# demo_dermis_main_testboard.net
KiCad netlist of a schematic drawn in Altium Designer
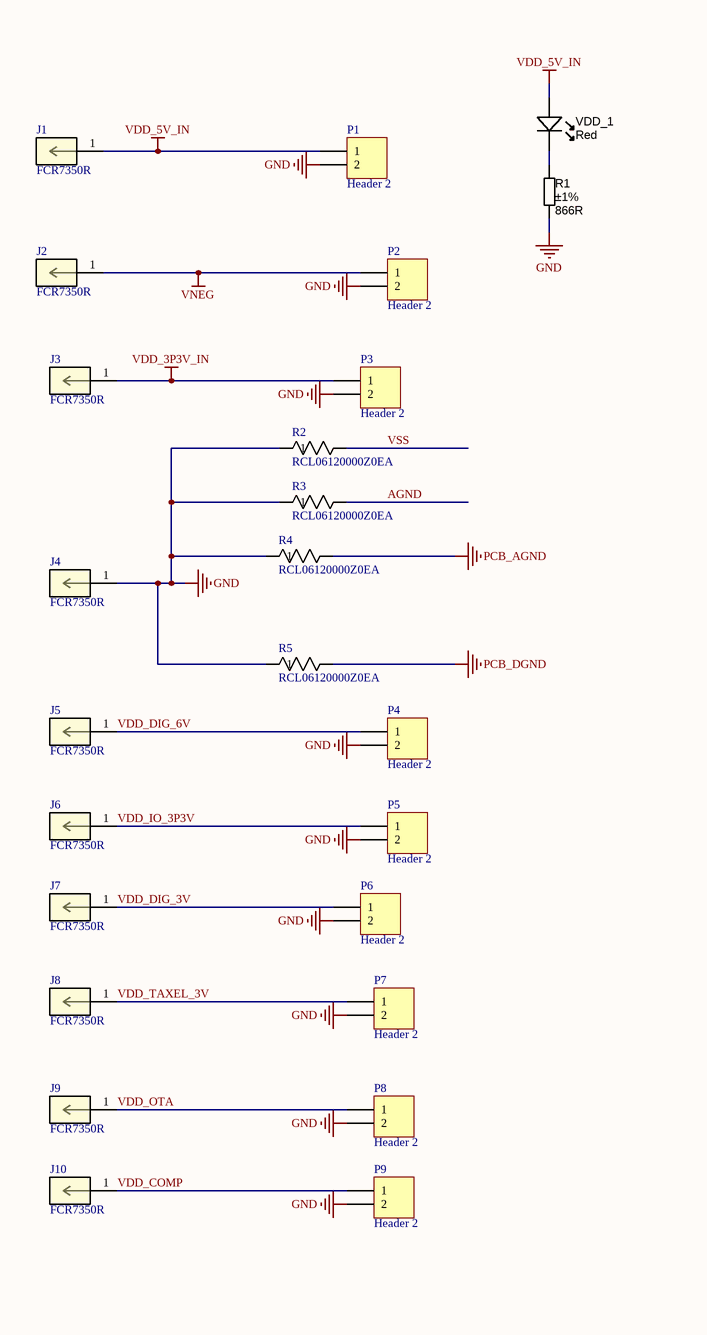
[diagram p0: demo_dermis_main_testboard.SchDoc, top left]
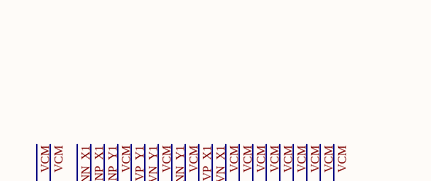
[diagram p1: demo_dermis_main_testboard.SchDoc, top right]
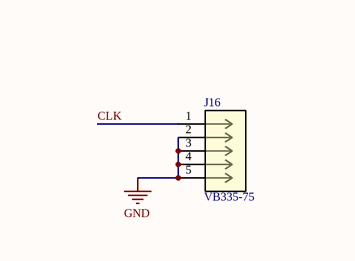
[diagram p2: demo_dermis_main_testboard.SchDoc, bottom middle]
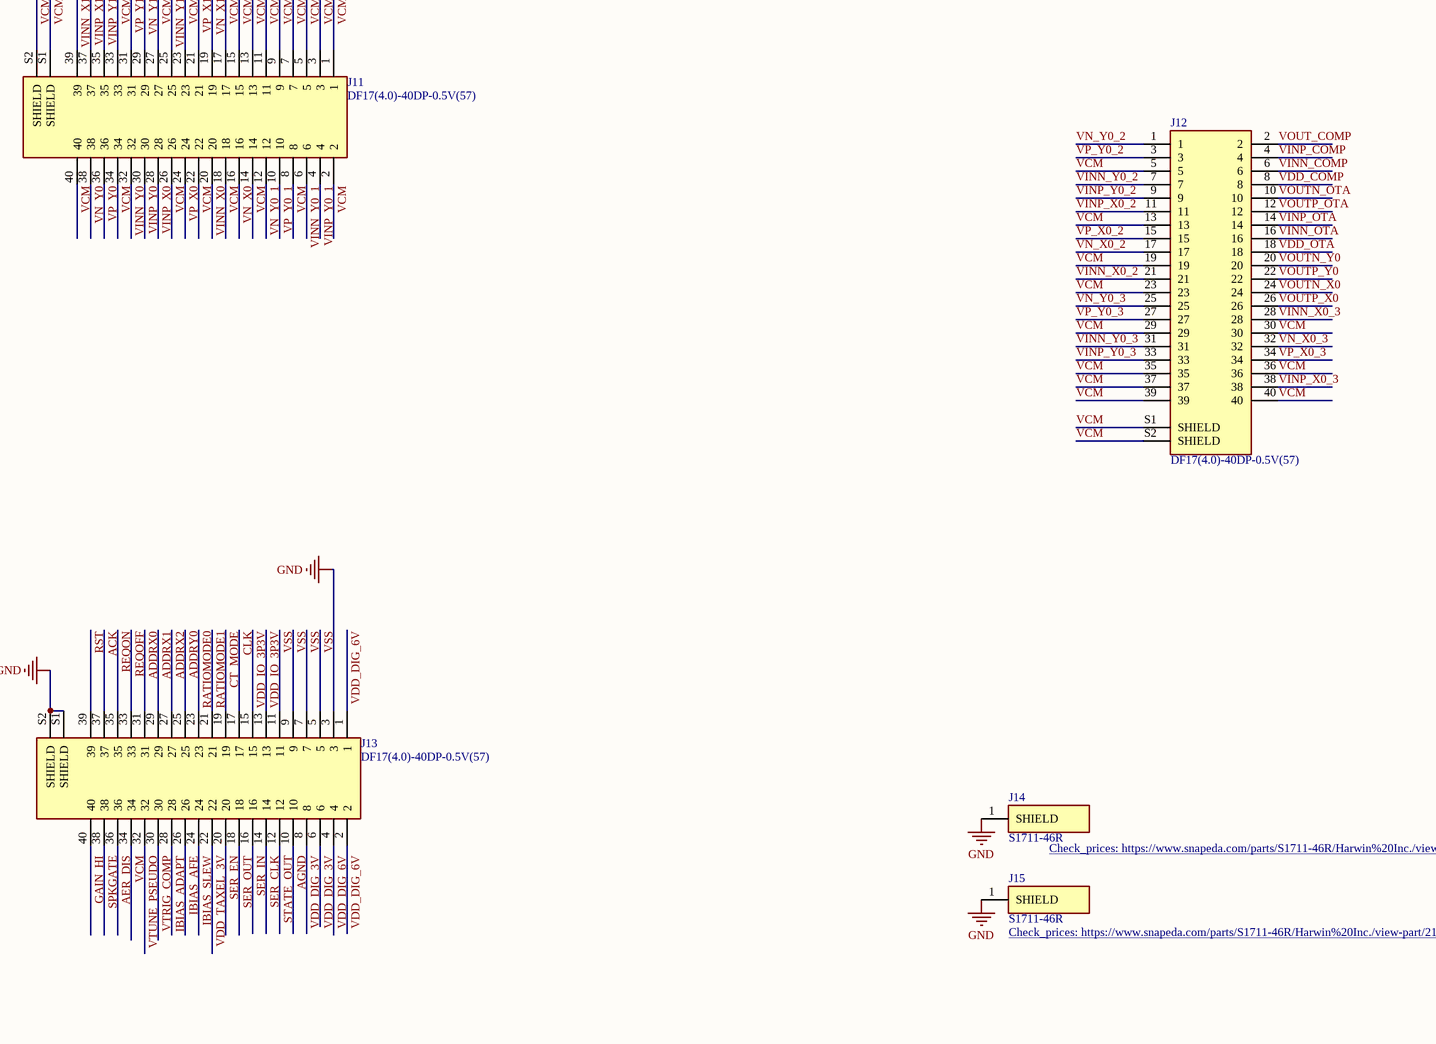
[diagram p3: demo_dermis_main_testboard.SchDoc, bottom right]

(export (version "E")
  (design (tool "Eeschema 10.0.6"))
  (components
    (comp (ref "J1")
      (value "FCR7350R")
      (footprint "CONN1_FCR7350R_CLF")
      (description "No Description Available")
      (fields (field (name "COPYRIGHT") "Copyright (C) 2022 Ultra Librarian. All rights reserved."))
      (libsource (lib "FCR7350B") (part "FCR7350R"))
    )
    (comp (ref "J2")
      (value "FCR7350R")
      (footprint "CONN1_FCR7350R_CLF")
      (description "No Description Available")
      (fields (field (name "COPYRIGHT") "Copyright (C) 2022 Ultra Librarian. All rights reserved."))
      (libsource (lib "FCR7350B") (part "FCR7350R"))
    )
    (comp (ref "J3")
      (value "FCR7350R")
      (footprint "CONN1_FCR7350R_CLF")
      (description "No Description Available")
      (fields (field (name "COPYRIGHT") "Copyright (C) 2022 Ultra Librarian. All rights reserved."))
      (libsource (lib "FCR7350B") (part "FCR7350R"))
    )
    (comp (ref "J4")
      (value "FCR7350R")
      (footprint "CONN1_FCR7350R_CLF")
      (description "No Description Available")
      (fields (field (name "COPYRIGHT") "Copyright (C) 2022 Ultra Librarian. All rights reserved."))
      (libsource (lib "FCR7350B") (part "FCR7350R"))
    )
    (comp (ref "J5")
      (value "FCR7350R")
      (footprint "CONN1_FCR7350R_CLF")
      (description "No Description Available")
      (fields (field (name "COPYRIGHT") "Copyright (C) 2022 Ultra Librarian. All rights reserved."))
      (libsource (lib "FCR7350B") (part "FCR7350R"))
    )
    (comp (ref "J6")
      (value "FCR7350R")
      (footprint "CONN1_FCR7350R_CLF")
      (description "No Description Available")
      (fields (field (name "COPYRIGHT") "Copyright (C) 2022 Ultra Librarian. All rights reserved."))
      (libsource (lib "FCR7350B") (part "FCR7350R"))
    )
    (comp (ref "J7")
      (value "FCR7350R")
      (footprint "CONN1_FCR7350R_CLF")
      (description "No Description Available")
      (fields (field (name "COPYRIGHT") "Copyright (C) 2022 Ultra Librarian. All rights reserved."))
      (libsource (lib "FCR7350B") (part "FCR7350R"))
    )
    (comp (ref "J8")
      (value "FCR7350R")
      (footprint "CONN1_FCR7350R_CLF")
      (description "No Description Available")
      (fields (field (name "COPYRIGHT") "Copyright (C) 2022 Ultra Librarian. All rights reserved."))
      (libsource (lib "FCR7350B") (part "FCR7350R"))
    )
    (comp (ref "J9")
      (value "FCR7350R")
      (footprint "CONN1_FCR7350R_CLF")
      (description "No Description Available")
      (fields (field (name "COPYRIGHT") "Copyright (C) 2022 Ultra Librarian. All rights reserved."))
      (libsource (lib "FCR7350B") (part "FCR7350R"))
    )
    (comp (ref "J10")
      (value "FCR7350R")
      (footprint "CONN1_FCR7350R_CLF")
      (description "No Description Available")
      (fields (field (name "COPYRIGHT") "Copyright (C) 2022 Ultra Librarian. All rights reserved."))
      (libsource (lib "FCR7350B") (part "FCR7350R"))
    )
    (comp (ref "J11")
      (value "DF17(4.0)-40DP-0.5V(57)")
      (footprint "HRS_DF17(4.0)-40DP-0.5V(57)")
      (libsource (lib "DF17_4.0_-40DP-0.5V_57_") (part "DF17(4.0)-40DP-0.5V(57)"))
    )
    (comp (ref "J12")
      (value "DF17(4.0)-40DP-0.5V(57)")
      (footprint "HRS_DF17(4.0)-40DP-0.5V(57)")
      (libsource (lib "") (part "DF17(4.0)-40DP-0.5V(57)_1"))
    )
    (comp (ref "J13")
      (value "DF17(4.0)-40DP-0.5V(57)")
      (footprint "HRS_DF17(4.0)-40DP-0.5V(57)")
      (libsource (lib "DF17_4.0_-40DP-0.5V_57_") (part "DF17(4.0)-40DP-0.5V(57)"))
    )
    (comp (ref "J14")
      (value "S1711-46R")
      (footprint "HARWIN_S1711-46R")
      (description "RFI SHIELD CLIP TIN SMD")
      (fields
        (field (name "MF") "Harwin Inc.")
        (field (name "CHECK_PRICES") "https://www.snapeda.com/parts/S1711-46R/Harwin%20Inc./view-part/2172610/?ref=eda")
      )
      (libsource (lib "S1711-46R") (part "S1711-46R"))
    )
    (comp (ref "J15")
      (value "S1711-46R")
      (footprint "HARWIN_S1711-46R")
      (description "RFI SHIELD CLIP TIN SMD")
      (fields
        (field (name "MF") "Harwin Inc.")
        (field (name "CHECK_PRICES") "https://www.snapeda.com/parts/S1711-46R/Harwin%20Inc./view-part/2172610/?ref=eda")
      )
      (libsource (lib "S1711-46R") (part "S1711-46R"))
    )
    (comp (ref "J16")
      (value "VB335-75")
      (footprint "CONN5_VB335_CIN")
      (description "No Description Available")
      (libsource (lib "VB335-75") (part "VB335-75"))
    )
    (comp (ref "P1")
      (value "Header 2")
      (footprint "HDR1X2")
      (description "Header, 2-Pin")
      (fields (field (name "PUBLISHER") "Altium Limited"))
      (libsource (lib "Miscellaneous Connectors") (part "Header 2"))
    )
    (comp (ref "P2")
      (value "Header 2")
      (footprint "HDR1X2")
      (description "Header, 2-Pin")
      (fields (field (name "PUBLISHER") "Altium Limited"))
      (libsource (lib "Miscellaneous Connectors") (part "Header 2"))
    )
    (comp (ref "P3")
      (value "Header 2")
      (footprint "HDR1X2")
      (description "Header, 2-Pin")
      (fields (field (name "PUBLISHER") "Altium Limited"))
      (libsource (lib "Miscellaneous Connectors") (part "Header 2"))
    )
    (comp (ref "P4")
      (value "Header 2")
      (footprint "HDR1X2")
      (description "Header, 2-Pin")
      (fields (field (name "PUBLISHER") "Altium Limited"))
      (libsource (lib "Miscellaneous Connectors") (part "Header 2"))
    )
    (comp (ref "P5")
      (value "Header 2")
      (footprint "HDR1X2")
      (description "Header, 2-Pin")
      (fields (field (name "PUBLISHER") "Altium Limited"))
      (libsource (lib "Miscellaneous Connectors") (part "Header 2"))
    )
    (comp (ref "P6")
      (value "Header 2")
      (footprint "HDR1X2")
      (description "Header, 2-Pin")
      (fields (field (name "PUBLISHER") "Altium Limited"))
      (libsource (lib "Miscellaneous Connectors") (part "Header 2"))
    )
    (comp (ref "P7")
      (value "Header 2")
      (footprint "HDR1X2")
      (description "Header, 2-Pin")
      (fields (field (name "PUBLISHER") "Altium Limited"))
      (libsource (lib "Miscellaneous Connectors") (part "Header 2"))
    )
    (comp (ref "P8")
      (value "Header 2")
      (footprint "HDR1X2")
      (description "Header, 2-Pin")
      (fields (field (name "PUBLISHER") "Altium Limited"))
      (libsource (lib "Miscellaneous Connectors") (part "Header 2"))
    )
    (comp (ref "P9")
      (value "Header 2")
      (footprint "HDR1X2")
      (description "Header, 2-Pin")
      (fields (field (name "PUBLISHER") "Altium Limited"))
      (libsource (lib "Miscellaneous Connectors") (part "Header 2"))
    )
    (comp (ref "R1")
      (value "866R")
      (footprint "RESC1608N")
      (description "Resistor SMD chip 866 Ohm 0.1W 1% 0603")
      (fields (field (name "TOLERANCE") "±1%") (field (name "Comment") "Thick Film"))
      (libsource (lib "MB - Misc") (part "RES_866R_0603_1%_1"))
    )
    (comp (ref "R2")
      (value "RCL06120000Z0EA")
      (footprint "RCL0612_VIS")
      (description "No Description Available")
      (libsource (lib "RCL06120000Z0EA") (part "RCL06120000Z0EA"))
    )
    (comp (ref "R3")
      (value "RCL06120000Z0EA")
      (footprint "RCL0612_VIS")
      (description "No Description Available")
      (libsource (lib "RCL06120000Z0EA") (part "RCL06120000Z0EA"))
    )
    (comp (ref "R4")
      (value "RCL06120000Z0EA")
      (footprint "RCL0612_VIS")
      (description "No Description Available")
      (libsource (lib "RCL06120000Z0EA") (part "RCL06120000Z0EA"))
    )
    (comp (ref "R5")
      (value "RCL06120000Z0EA")
      (footprint "RCL0612_VIS")
      (description "No Description Available")
      (libsource (lib "RCL06120000Z0EA") (part "RCL06120000Z0EA"))
    )
    (comp (ref "VDD_1")
      (value "Red")
      (footprint "LED-0603-RED")
      (description "LED 0603 SMD Hyper Red 630nm 220mcd 20mA")
      (libsource (lib "PBL - Light Sources") (part "LED_SMD_Red_0603_220mcd"))
    )
  )
  (nets
    (net (code "1") (name "/ACK") (class "Default")
      (node (ref "J13") (pin "37") (pinfunction "37_37") (pintype "passive"))
    )
    (net (code "2") (name "/ADDRX0") (class "Default")
      (node (ref "J13") (pin "31") (pinfunction "31_31") (pintype "passive"))
    )
    (net (code "3") (name "/ADDRX1") (class "Default")
      (node (ref "J13") (pin "29") (pinfunction "29_29") (pintype "passive"))
    )
    (net (code "4") (name "/ADDRX2") (class "Default")
      (node (ref "J13") (pin "27") (pinfunction "27_27") (pintype "passive"))
    )
    (net (code "5") (name "/ADDRY0") (class "Default")
      (node (ref "J13") (pin "25") (pinfunction "25_25") (pintype "passive"))
    )
    (net (code "6") (name "/AER_DIS") (class "Default")
      (node (ref "J13") (pin "36") (pinfunction "36_36") (pintype "passive"))
    )
    (net (code "7") (name "/AGND") (class "Default")
      (node (ref "J13") (pin "10") (pinfunction "10_10") (pintype "passive"))
      (node (ref "R3") (pin "2") (pinfunction "2_2") (pintype "passive"))
    )
    (net (code "8") (name "/CLK") (class "Default")
      (node (ref "J13") (pin "17") (pinfunction "17_17") (pintype "passive"))
      (node (ref "J16") (pin "1") (pinfunction "1_1") (pintype "passive"))
    )
    (net (code "9") (name "/CT_MODE") (class "Default")
      (node (ref "J13") (pin "19") (pinfunction "19_19") (pintype "passive"))
    )
    (net (code "10") (name "/GAIN_HI") (class "Default")
      (node (ref "J13") (pin "40") (pinfunction "40_40") (pintype "passive"))
    )
    (net (code "11") (name "/IBIAS_ADAPT") (class "Default")
      (node (ref "J13") (pin "28") (pinfunction "28_28") (pintype "passive"))
    )
    (net (code "12") (name "/IBIAS_AFE") (class "Default")
      (node (ref "J13") (pin "26") (pinfunction "26_26") (pintype "passive"))
    )
    (net (code "13") (name "/IBIAS_SLEW") (class "Default")
      (node (ref "J13") (pin "24") (pinfunction "24_24") (pintype "passive"))
    )
    (net (code "14") (name "/RATIOMODE0") (class "Default")
      (node (ref "J13") (pin "23") (pinfunction "23_23") (pintype "passive"))
    )
    (net (code "15") (name "/RATIOMODE1") (class "Default")
      (node (ref "J13") (pin "21") (pinfunction "21_21") (pintype "passive"))
    )
    (net (code "16") (name "/REQOFF") (class "Default")
      (node (ref "J13") (pin "33") (pinfunction "33_33") (pintype "passive"))
    )
    (net (code "17") (name "/REQON") (class "Default")
      (node (ref "J13") (pin "35") (pinfunction "35_35") (pintype "passive"))
    )
    (net (code "18") (name "/RST") (class "Default")
      (node (ref "J13") (pin "39") (pinfunction "39_39") (pintype "passive"))
    )
    (net (code "19") (name "/SER_CLK") (class "Default")
      (node (ref "J13") (pin "14") (pinfunction "14_14") (pintype "passive"))
    )
    (net (code "20") (name "/SER_EN") (class "Default")
      (node (ref "J13") (pin "20") (pinfunction "20_20") (pintype "passive"))
    )
    (net (code "21") (name "/SER_IN") (class "Default")
      (node (ref "J13") (pin "16") (pinfunction "16_16") (pintype "passive"))
    )
    (net (code "22") (name "/SER_OUT") (class "Default")
      (node (ref "J13") (pin "18") (pinfunction "18_18") (pintype "passive"))
    )
    (net (code "23") (name "/SPKGATE") (class "Default")
      (node (ref "J13") (pin "38") (pinfunction "38_38") (pintype "passive"))
    )
    (net (code "24") (name "/STATE_OUT") (class "Default")
      (node (ref "J13") (pin "12") (pinfunction "12_12") (pintype "passive"))
    )
    (net (code "25") (name "/VCM") (class "Default")
      (node (ref "J11") (pin "1") (pinfunction "1_1") (pintype "passive"))
      (node (ref "J11") (pin "11") (pinfunction "11_11") (pintype "passive"))
      (node (ref "J11") (pin "13") (pinfunction "13_13") (pintype "passive"))
      (node (ref "J11") (pin "14") (pinfunction "14_14") (pintype "passive"))
      (node (ref "J11") (pin "15") (pinfunction "15_15") (pintype "passive"))
      (node (ref "J11") (pin "17") (pinfunction "17_17") (pintype "passive"))
      (node (ref "J11") (pin "18") (pinfunction "18_18") (pintype "passive"))
      (node (ref "J11") (pin "2") (pinfunction "2_2") (pintype "passive"))
      (node (ref "J11") (pin "22") (pinfunction "22_22") (pintype "passive"))
      (node (ref "J11") (pin "23") (pinfunction "23_23") (pintype "passive"))
      (node (ref "J11") (pin "26") (pinfunction "26_26") (pintype "passive"))
      (node (ref "J11") (pin "27") (pinfunction "27_27") (pintype "passive"))
      (node (ref "J11") (pin "3") (pinfunction "3_3") (pintype "passive"))
      (node (ref "J11") (pin "33") (pinfunction "33_33") (pintype "passive"))
      (node (ref "J11") (pin "34") (pinfunction "34_34") (pintype "passive"))
      (node (ref "J11") (pin "40") (pinfunction "40_40") (pintype "passive"))
      (node (ref "J11") (pin "5") (pinfunction "5_5") (pintype "passive"))
      (node (ref "J11") (pin "7") (pinfunction "7_7") (pintype "passive"))
      (node (ref "J11") (pin "8") (pinfunction "8_8") (pintype "passive"))
      (node (ref "J11") (pin "9") (pinfunction "9_9") (pintype "passive"))
      (node (ref "J11") (pin "S1") (pinfunction "SHIELD_S1") (pintype "passive"))
      (node (ref "J11") (pin "S2") (pinfunction "SHIELD_S2") (pintype "passive"))
      (node (ref "J12") (pin "13") (pinfunction "13_13") (pintype "passive"))
      (node (ref "J12") (pin "19") (pinfunction "19_19") (pintype "passive"))
      (node (ref "J12") (pin "23") (pinfunction "23_23") (pintype "passive"))
      (node (ref "J12") (pin "29") (pinfunction "29_29") (pintype "passive"))
      (node (ref "J12") (pin "30") (pinfunction "30_30") (pintype "passive"))
      (node (ref "J12") (pin "35") (pinfunction "35_35") (pintype "passive"))
      (node (ref "J12") (pin "36") (pinfunction "36_36") (pintype "passive"))
      (node (ref "J12") (pin "37") (pinfunction "37_37") (pintype "passive"))
      (node (ref "J12") (pin "39") (pinfunction "39_39") (pintype "passive"))
      (node (ref "J12") (pin "40") (pinfunction "40_40") (pintype "passive"))
      (node (ref "J12") (pin "5") (pinfunction "5_5") (pintype "passive"))
      (node (ref "J12") (pin "S1") (pinfunction "SHIELD_S1") (pintype "passive"))
      (node (ref "J12") (pin "S2") (pinfunction "SHIELD_S2") (pintype "passive"))
      (node (ref "J13") (pin "34") (pinfunction "34_34") (pintype "passive"))
    )
    (net (code "26") (name "/VDD_COMP") (class "Default")
      (node (ref "J10") (pin "1") (pinfunction "1_1") (pintype "passive"))
      (node (ref "J12") (pin "8") (pinfunction "8_8") (pintype "passive"))
      (node (ref "P9") (pin "1") (pinfunction "1_1") (pintype "passive"))
    )
    (net (code "27") (name "/VDD_DIG_3V") (class "Default")
      (node (ref "J13") (pin "6") (pinfunction "6_6") (pintype "passive"))
      (node (ref "J13") (pin "8") (pinfunction "8_8") (pintype "passive"))
      (node (ref "J7") (pin "1") (pinfunction "1_1") (pintype "passive"))
      (node (ref "P6") (pin "1") (pinfunction "1_1") (pintype "passive"))
    )
    (net (code "28") (name "/VDD_DIG_6V") (class "Default")
      (node (ref "J13") (pin "1") (pinfunction "1_1") (pintype "passive"))
      (node (ref "J13") (pin "2") (pinfunction "2_2") (pintype "passive"))
      (node (ref "J13") (pin "4") (pinfunction "4_4") (pintype "passive"))
      (node (ref "J5") (pin "1") (pinfunction "1_1") (pintype "passive"))
      (node (ref "P4") (pin "1") (pinfunction "1_1") (pintype "passive"))
    )
    (net (code "29") (name "/VDD_IO_3P3V") (class "Default")
      (node (ref "J13") (pin "13") (pinfunction "13_13") (pintype "passive"))
      (node (ref "J13") (pin "15") (pinfunction "15_15") (pintype "passive"))
      (node (ref "J6") (pin "1") (pinfunction "1_1") (pintype "passive"))
      (node (ref "P5") (pin "1") (pinfunction "1_1") (pintype "passive"))
    )
    (net (code "30") (name "/VDD_OTA") (class "Default")
      (node (ref "J12") (pin "18") (pinfunction "18_18") (pintype "passive"))
      (node (ref "J9") (pin "1") (pinfunction "1_1") (pintype "passive"))
      (node (ref "P8") (pin "1") (pinfunction "1_1") (pintype "passive"))
    )
    (net (code "31") (name "/VDD_TAXEL_3V") (class "Default")
      (node (ref "J13") (pin "22") (pinfunction "22_22") (pintype "passive"))
      (node (ref "J8") (pin "1") (pinfunction "1_1") (pintype "passive"))
      (node (ref "P7") (pin "1") (pinfunction "1_1") (pintype "passive"))
    )
    (net (code "32") (name "/VINN_COMP") (class "Default")
      (node (ref "J12") (pin "6") (pinfunction "6_6") (pintype "passive"))
    )
    (net (code "33") (name "/VINN_OTA") (class "Default")
      (node (ref "J12") (pin "16") (pinfunction "16_16") (pintype "passive"))
    )
    (net (code "34") (name "/VINN_X0") (class "Default")
      (node (ref "J11") (pin "20") (pinfunction "20_20") (pintype "passive"))
    )
    (net (code "35") (name "/VINN_X0_2") (class "Default")
      (node (ref "J12") (pin "21") (pinfunction "21_21") (pintype "passive"))
    )
    (net (code "36") (name "/VINN_X0_3") (class "Default")
      (node (ref "J12") (pin "28") (pinfunction "28_28") (pintype "passive"))
    )
    (net (code "37") (name "/VINN_X1") (class "Default")
      (node (ref "J11") (pin "39") (pinfunction "39_39") (pintype "passive"))
    )
    (net (code "38") (name "/VINN_Y0") (class "Default")
      (node (ref "J11") (pin "32") (pinfunction "32_32") (pintype "passive"))
    )
    (net (code "39") (name "/VINN_Y0_1") (class "Default")
      (node (ref "J11") (pin "6") (pinfunction "6_6") (pintype "passive"))
    )
    (net (code "40") (name "/VINN_Y0_2") (class "Default")
      (node (ref "J12") (pin "7") (pinfunction "7_7") (pintype "passive"))
    )
    (net (code "41") (name "/VINN_Y0_3") (class "Default")
      (node (ref "J12") (pin "31") (pinfunction "31_31") (pintype "passive"))
    )
    (net (code "42") (name "/VINN_Y1") (class "Default")
      (node (ref "J11") (pin "25") (pinfunction "25_25") (pintype "passive"))
    )
    (net (code "43") (name "/VINP_COMP") (class "Default")
      (node (ref "J12") (pin "4") (pinfunction "4_4") (pintype "passive"))
    )
    (net (code "44") (name "/VINP_OTA") (class "Default")
      (node (ref "J12") (pin "14") (pinfunction "14_14") (pintype "passive"))
    )
    (net (code "45") (name "/VINP_X0") (class "Default")
      (node (ref "J11") (pin "28") (pinfunction "28_28") (pintype "passive"))
    )
    (net (code "46") (name "/VINP_X0_2") (class "Default")
      (node (ref "J12") (pin "11") (pinfunction "11_11") (pintype "passive"))
    )
    (net (code "47") (name "/VINP_X0_3") (class "Default")
      (node (ref "J12") (pin "38") (pinfunction "38_38") (pintype "passive"))
    )
    (net (code "48") (name "/VINP_X1") (class "Default")
      (node (ref "J11") (pin "37") (pinfunction "37_37") (pintype "passive"))
    )
    (net (code "49") (name "/VINP_Y0") (class "Default")
      (node (ref "J11") (pin "30") (pinfunction "30_30") (pintype "passive"))
    )
    (net (code "50") (name "/VINP_Y0_1") (class "Default")
      (node (ref "J11") (pin "4") (pinfunction "4_4") (pintype "passive"))
    )
    (net (code "51") (name "/VINP_Y0_2") (class "Default")
      (node (ref "J12") (pin "9") (pinfunction "9_9") (pintype "passive"))
    )
    (net (code "52") (name "/VINP_Y0_3") (class "Default")
      (node (ref "J12") (pin "33") (pinfunction "33_33") (pintype "passive"))
    )
    (net (code "53") (name "/VINP_Y1") (class "Default")
      (node (ref "J11") (pin "35") (pinfunction "35_35") (pintype "passive"))
    )
    (net (code "54") (name "/VN_X0") (class "Default")
      (node (ref "J11") (pin "16") (pinfunction "16_16") (pintype "passive"))
    )
    (net (code "55") (name "/VN_X0_2") (class "Default")
      (node (ref "J12") (pin "17") (pinfunction "17_17") (pintype "passive"))
    )
    (net (code "56") (name "/VN_X0_3") (class "Default")
      (node (ref "J12") (pin "32") (pinfunction "32_32") (pintype "passive"))
    )
    (net (code "57") (name "/VN_X1") (class "Default")
      (node (ref "J11") (pin "19") (pinfunction "19_19") (pintype "passive"))
    )
    (net (code "58") (name "/VN_Y0") (class "Default")
      (node (ref "J11") (pin "38") (pinfunction "38_38") (pintype "passive"))
    )
    (net (code "59") (name "/VN_Y0_1") (class "Default")
      (node (ref "J11") (pin "12") (pinfunction "12_12") (pintype "passive"))
    )
    (net (code "60") (name "/VN_Y0_2") (class "Default")
      (node (ref "J12") (pin "1") (pinfunction "1_1") (pintype "passive"))
    )
    (net (code "61") (name "/VN_Y0_3") (class "Default")
      (node (ref "J12") (pin "25") (pinfunction "25_25") (pintype "passive"))
    )
    (net (code "62") (name "/VN_Y1") (class "Default")
      (node (ref "J11") (pin "29") (pinfunction "29_29") (pintype "passive"))
    )
    (net (code "63") (name "/VOUTN_OTA") (class "Default")
      (node (ref "J12") (pin "10") (pinfunction "10_10") (pintype "passive"))
    )
    (net (code "64") (name "/VOUTN_X0") (class "Default")
      (node (ref "J12") (pin "24") (pinfunction "24_24") (pintype "passive"))
    )
    (net (code "65") (name "/VOUTN_Y0") (class "Default")
      (node (ref "J12") (pin "20") (pinfunction "20_20") (pintype "passive"))
    )
    (net (code "66") (name "/VOUTP_OTA") (class "Default")
      (node (ref "J12") (pin "12") (pinfunction "12_12") (pintype "passive"))
    )
    (net (code "67") (name "/VOUTP_X0") (class "Default")
      (node (ref "J12") (pin "26") (pinfunction "26_26") (pintype "passive"))
    )
    (net (code "68") (name "/VOUTP_Y0") (class "Default")
      (node (ref "J12") (pin "22") (pinfunction "22_22") (pintype "passive"))
    )
    (net (code "69") (name "/VOUT_COMP") (class "Default")
      (node (ref "J12") (pin "2") (pinfunction "2_2") (pintype "passive"))
    )
    (net (code "70") (name "/VP_X0") (class "Default")
      (node (ref "J11") (pin "24") (pinfunction "24_24") (pintype "passive"))
    )
    (net (code "71") (name "/VP_X0_2") (class "Default")
      (node (ref "J12") (pin "15") (pinfunction "15_15") (pintype "passive"))
    )
    (net (code "72") (name "/VP_X0_3") (class "Default")
      (node (ref "J12") (pin "34") (pinfunction "34_34") (pintype "passive"))
    )
    (net (code "73") (name "/VP_X1") (class "Default")
      (node (ref "J11") (pin "21") (pinfunction "21_21") (pintype "passive"))
    )
    (net (code "74") (name "/VP_Y0") (class "Default")
      (node (ref "J11") (pin "36") (pinfunction "36_36") (pintype "passive"))
    )
    (net (code "75") (name "/VP_Y0_1") (class "Default")
      (node (ref "J11") (pin "10") (pinfunction "10_10") (pintype "passive"))
    )
    (net (code "76") (name "/VP_Y0_2") (class "Default")
      (node (ref "J12") (pin "3") (pinfunction "3_3") (pintype "passive"))
    )
    (net (code "77") (name "/VP_Y0_3") (class "Default")
      (node (ref "J12") (pin "27") (pinfunction "27_27") (pintype "passive"))
    )
    (net (code "78") (name "/VP_Y1") (class "Default")
      (node (ref "J11") (pin "31") (pinfunction "31_31") (pintype "passive"))
    )
    (net (code "79") (name "/VSS") (class "Default")
      (node (ref "J13") (pin "11") (pinfunction "11_11") (pintype "passive"))
      (node (ref "J13") (pin "5") (pinfunction "5_5") (pintype "passive"))
      (node (ref "J13") (pin "7") (pinfunction "7_7") (pintype "passive"))
      (node (ref "J13") (pin "9") (pinfunction "9_9") (pintype "passive"))
      (node (ref "R2") (pin "2") (pinfunction "2_2") (pintype "passive"))
    )
    (net (code "80") (name "/VTRIG_COMP") (class "Default")
      (node (ref "J13") (pin "30") (pinfunction "30_30") (pintype "passive"))
    )
    (net (code "81") (name "/VTUNE_PSEUDO") (class "Default")
      (node (ref "J13") (pin "32") (pinfunction "32_32") (pintype "passive"))
    )
    (net (code "82") (name "GND") (class "Default")
      (node (ref "J13") (pin "3") (pinfunction "3_3") (pintype "passive"))
      (node (ref "J13") (pin "S1") (pinfunction "SHIELD_S1") (pintype "passive"))
      (node (ref "J13") (pin "S2") (pinfunction "SHIELD_S2") (pintype "passive"))
      (node (ref "J14") (pin "1") (pinfunction "SHIELD_1") (pintype "passive"))
      (node (ref "J15") (pin "1") (pinfunction "SHIELD_1") (pintype "passive"))
      (node (ref "J16") (pin "2") (pinfunction "2_2") (pintype "passive"))
      (node (ref "J16") (pin "3") (pinfunction "3_3") (pintype "passive"))
      (node (ref "J16") (pin "4") (pinfunction "4_4") (pintype "passive"))
      (node (ref "J16") (pin "5") (pinfunction "5_5") (pintype "passive"))
      (node (ref "J4") (pin "1") (pinfunction "1_1") (pintype "passive"))
      (node (ref "P1") (pin "2") (pinfunction "2_2") (pintype "passive"))
      (node (ref "P2") (pin "2") (pinfunction "2_2") (pintype "passive"))
      (node (ref "P3") (pin "2") (pinfunction "2_2") (pintype "passive"))
      (node (ref "P4") (pin "2") (pinfunction "2_2") (pintype "passive"))
      (node (ref "P5") (pin "2") (pinfunction "2_2") (pintype "passive"))
      (node (ref "P6") (pin "2") (pinfunction "2_2") (pintype "passive"))
      (node (ref "P7") (pin "2") (pinfunction "2_2") (pintype "passive"))
      (node (ref "P8") (pin "2") (pinfunction "2_2") (pintype "passive"))
      (node (ref "P9") (pin "2") (pinfunction "2_2") (pintype "passive"))
      (node (ref "R1") (pin "2") (pinfunction "2_2") (pintype "passive"))
      (node (ref "R2") (pin "1") (pinfunction "1_1") (pintype "passive"))
      (node (ref "R3") (pin "1") (pinfunction "1_1") (pintype "passive"))
      (node (ref "R4") (pin "1") (pinfunction "1_1") (pintype "passive"))
      (node (ref "R5") (pin "1") (pinfunction "1_1") (pintype "passive"))
    )
    (net (code "83") (name "Net-(R1-Pad1)") (class "Default")
      (node (ref "R1") (pin "1") (pinfunction "1_1") (pintype "passive"))
      (node (ref "VDD_1") (pin "K") (pinfunction "K_K") (pintype "passive"))
    )
    (net (code "84") (name "PCB_AGND") (class "Default")
      (node (ref "R4") (pin "2") (pinfunction "2_2") (pintype "passive"))
    )
    (net (code "85") (name "PCB_DGND") (class "Default")
      (node (ref "R5") (pin "2") (pinfunction "2_2") (pintype "passive"))
    )
    (net (code "86") (name "VDD_3P3V_IN") (class "Default")
      (node (ref "J3") (pin "1") (pinfunction "1_1") (pintype "passive"))
      (node (ref "P3") (pin "1") (pinfunction "1_1") (pintype "passive"))
    )
    (net (code "87") (name "VDD_5V_IN") (class "Default")
      (node (ref "J1") (pin "1") (pinfunction "1_1") (pintype "passive"))
      (node (ref "P1") (pin "1") (pinfunction "1_1") (pintype "passive"))
      (node (ref "VDD_1") (pin "A") (pinfunction "A_A") (pintype "passive"))
    )
    (net (code "88") (name "VNEG") (class "Default")
      (node (ref "J2") (pin "1") (pinfunction "1_1") (pintype "passive"))
      (node (ref "P2") (pin "1") (pinfunction "1_1") (pintype "passive"))
    )
  )
)
